# RC_Transmitter_TX_FINAL_v4_4.net
KiCad netlist of a schematic drawn in EAGLE
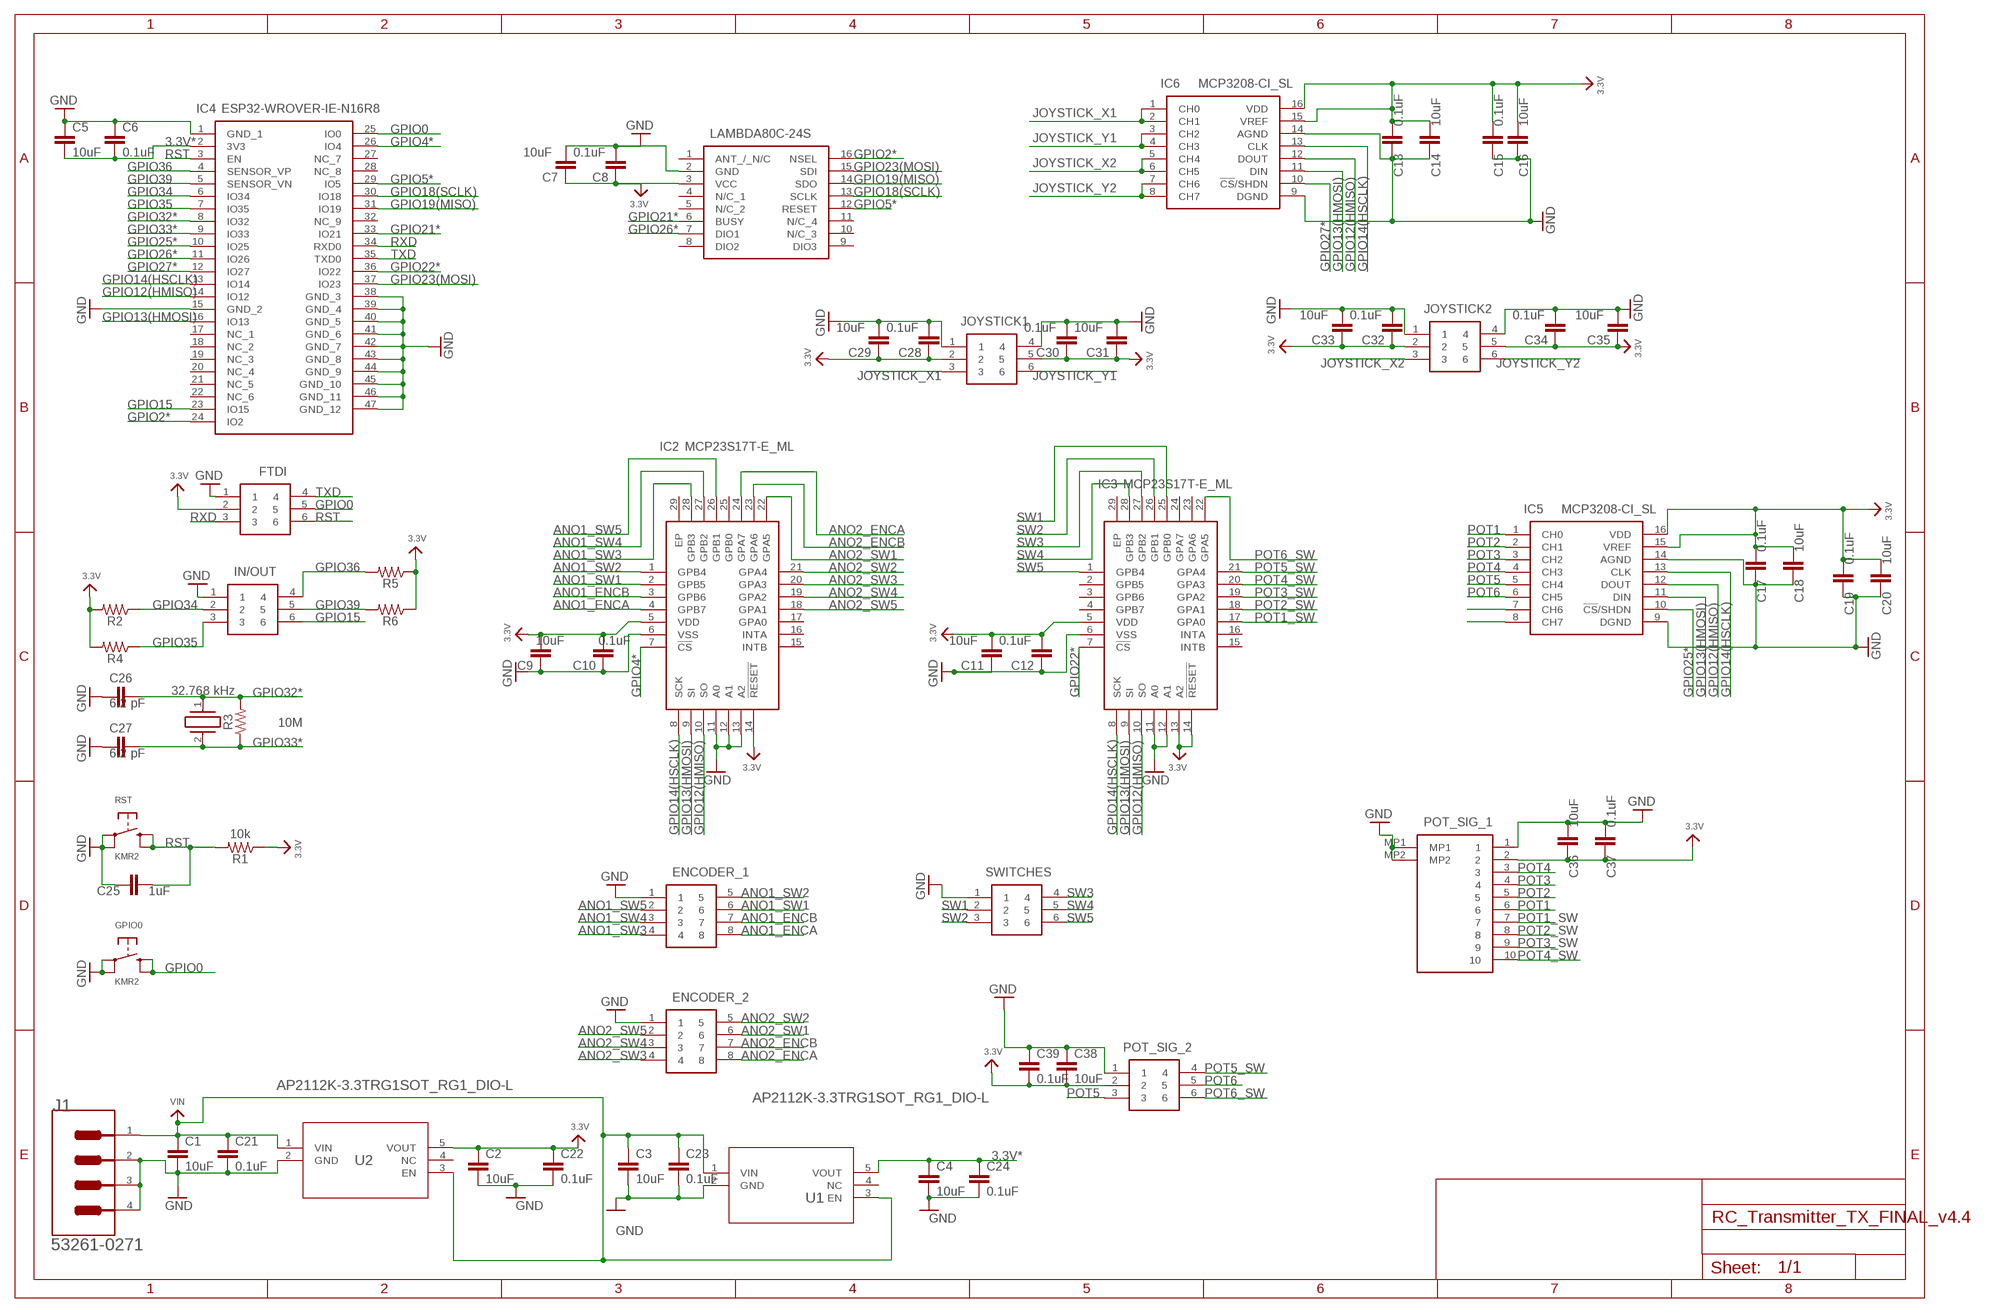
[diagram p0: schematic, sheet 1]

(export (version "E")
  (design (tool "Eeschema 10.0.6"))
  (components
    (comp (ref "C1")
      (value "10uF")
      (footprint "eagle-import:0805")
      (libsource (lib "eagle-import") (part "10UF-0805-10V-10%"))
    )
    (comp (ref "C2")
      (value "10uF")
      (footprint "eagle-import:0805")
      (libsource (lib "eagle-import") (part "10UF-0805-10V-10%"))
    )
    (comp (ref "C3")
      (value "10uF")
      (footprint "eagle-import:0805")
      (libsource (lib "eagle-import") (part "10UF-0805-10V-10%"))
    )
    (comp (ref "C4")
      (value "10uF")
      (footprint "eagle-import:0805")
      (libsource (lib "eagle-import") (part "10UF-0805-10V-10%"))
    )
    (comp (ref "C5")
      (value "10uF")
      (footprint "eagle-import:0805")
      (libsource (lib "eagle-import") (part "10UF-0805-10V-10%"))
    )
    (comp (ref "C6")
      (value "0.1uF")
      (footprint "eagle-import:0805")
      (libsource (lib "eagle-import") (part "10UF-0805-10V-10%"))
    )
    (comp (ref "C7")
      (value "10uF")
      (footprint "eagle-import:0805")
      (libsource (lib "eagle-import") (part "10UF-0805-10V-10%"))
    )
    (comp (ref "C8")
      (value "0.1uF")
      (footprint "eagle-import:0805")
      (libsource (lib "eagle-import") (part "10UF-0805-10V-10%"))
    )
    (comp (ref "C9")
      (value "10uF")
      (footprint "eagle-import:0805")
      (libsource (lib "eagle-import") (part "10UF-0805-10V-10%"))
    )
    (comp (ref "C10")
      (value "0.1uF")
      (footprint "eagle-import:0805")
      (libsource (lib "eagle-import") (part "10UF-0805-10V-10%"))
    )
    (comp (ref "C11")
      (value "10uF")
      (footprint "eagle-import:0805")
      (libsource (lib "eagle-import") (part "10UF-0805-10V-10%"))
    )
    (comp (ref "C12")
      (value "0.1uF")
      (footprint "eagle-import:0805")
      (libsource (lib "eagle-import") (part "10UF-0805-10V-10%"))
    )
    (comp (ref "C13")
      (value "0.1uF")
      (footprint "eagle-import:0805")
      (libsource (lib "eagle-import") (part "10UF-0805-10V-10%"))
    )
    (comp (ref "C14")
      (value "10uF")
      (footprint "eagle-import:0805")
      (libsource (lib "eagle-import") (part "10UF-0805-10V-10%"))
    )
    (comp (ref "C15")
      (value "0.1uF")
      (footprint "eagle-import:0805")
      (libsource (lib "eagle-import") (part "10UF-0805-10V-10%"))
    )
    (comp (ref "C16")
      (value "10uF")
      (footprint "eagle-import:0805")
      (libsource (lib "eagle-import") (part "10UF-0805-10V-10%"))
    )
    (comp (ref "C17")
      (value "0.1uF")
      (footprint "eagle-import:0805")
      (libsource (lib "eagle-import") (part "10UF-0805-10V-10%"))
    )
    (comp (ref "C18")
      (value "10uF")
      (footprint "eagle-import:0805")
      (libsource (lib "eagle-import") (part "10UF-0805-10V-10%"))
    )
    (comp (ref "C19")
      (value "0.1uF")
      (footprint "eagle-import:0805")
      (libsource (lib "eagle-import") (part "10UF-0805-10V-10%"))
    )
    (comp (ref "C20")
      (value "10uF")
      (footprint "eagle-import:0805")
      (libsource (lib "eagle-import") (part "10UF-0805-10V-10%"))
    )
    (comp (ref "C21")
      (value "0.1uF")
      (footprint "eagle-import:0805")
      (libsource (lib "eagle-import") (part "10UF-0805-10V-10%"))
    )
    (comp (ref "C22")
      (value "0.1uF")
      (footprint "eagle-import:0805")
      (libsource (lib "eagle-import") (part "10UF-0805-10V-10%"))
    )
    (comp (ref "C23")
      (value "0.1uF")
      (footprint "eagle-import:0805")
      (libsource (lib "eagle-import") (part "10UF-0805-10V-10%"))
    )
    (comp (ref "C24")
      (value "0.1uF")
      (footprint "eagle-import:0805")
      (libsource (lib "eagle-import") (part "10UF-0805-10V-10%"))
    )
    (comp (ref "C25")
      (value "1uF")
      (footprint "eagle-import:0805")
      (libsource (lib "eagle-import") (part "10UF-0805-10V-10%"))
    )
    (comp (ref "C26")
      (value "6.2 pF")
      (footprint "eagle-import:0805")
      (libsource (lib "eagle-import") (part "10UF-0805-10V-10%"))
    )
    (comp (ref "C27")
      (value "6.2 pF")
      (footprint "eagle-import:0805")
      (libsource (lib "eagle-import") (part "10UF-0805-10V-10%"))
    )
    (comp (ref "C28")
      (value "0.1uF")
      (footprint "eagle-import:0805")
      (libsource (lib "eagle-import") (part "10UF-0805-10V-10%"))
    )
    (comp (ref "C29")
      (value "10uF")
      (footprint "eagle-import:0805")
      (libsource (lib "eagle-import") (part "10UF-0805-10V-10%"))
    )
    (comp (ref "C30")
      (value "0.1uF")
      (footprint "eagle-import:0805")
      (libsource (lib "eagle-import") (part "10UF-0805-10V-10%"))
    )
    (comp (ref "C31")
      (value "10uF")
      (footprint "eagle-import:0805")
      (libsource (lib "eagle-import") (part "10UF-0805-10V-10%"))
    )
    (comp (ref "C32")
      (value "0.1uF")
      (footprint "eagle-import:0805")
      (libsource (lib "eagle-import") (part "10UF-0805-10V-10%"))
    )
    (comp (ref "C33")
      (value "10uF")
      (footprint "eagle-import:0805")
      (libsource (lib "eagle-import") (part "10UF-0805-10V-10%"))
    )
    (comp (ref "C34")
      (value "0.1uF")
      (footprint "eagle-import:0805")
      (libsource (lib "eagle-import") (part "10UF-0805-10V-10%"))
    )
    (comp (ref "C35")
      (value "10uF")
      (footprint "eagle-import:0805")
      (libsource (lib "eagle-import") (part "10UF-0805-10V-10%"))
    )
    (comp (ref "C36")
      (value "10uF")
      (footprint "eagle-import:0805")
      (libsource (lib "eagle-import") (part "10UF-0805-10V-10%"))
    )
    (comp (ref "C37")
      (value "0.1uF")
      (footprint "eagle-import:0805")
      (libsource (lib "eagle-import") (part "10UF-0805-10V-10%"))
    )
    (comp (ref "C38")
      (value "10uF")
      (footprint "eagle-import:0805")
      (libsource (lib "eagle-import") (part "10UF-0805-10V-10%"))
    )
    (comp (ref "C39")
      (value "0.1uF")
      (footprint "eagle-import:0805")
      (libsource (lib "eagle-import") (part "10UF-0805-10V-10%"))
    )
    (comp (ref "CRYSTAL")
      (value "32.768 kHz")
      (footprint "eagle-import:ECX327CDX1293")
      (fields
        (field (name "ARROW_PART_NUMBER") "ECX-.327-CDX-1293")
        (field (name "MOUSER_PART_NUMBER") "520-ECX-.327CDX-1293")
        (field (name "ARROW_PART_NUMBER_1") "Crystal")
      )
      (libsource (lib "eagle-import") (part "ECX-.327-CDX-1293"))
    )
    (comp (ref "ENCODER_1")
      (value "0532610871")
      (footprint "eagle-import:53261-0871")
      (libsource (lib "eagle-import") (part "0532610871"))
    )
    (comp (ref "ENCODER_2")
      (value "0532610871")
      (footprint "eagle-import:53261-0871")
      (libsource (lib "eagle-import") (part "0532610871"))
    )
    (comp (ref "FTDI")
      (value "0532610671")
      (footprint "eagle-import:0532610671")
      (libsource (lib "eagle-import") (part "0532610671"))
    )
    (comp (ref "GPIO0")
      (value "KMR2")
      (footprint "eagle-import:BTN_KMR2_4.6X2.8")
      (libsource (lib "eagle-import") (part "SWITCH_TACT_SMT4.6X2.8"))
    )
    (comp (ref "IC1")
      (value "LAMBDA80C-24S")
      (footprint "eagle-import:LAMBDA80C24S")
      (fields (field (name "MOUSER_PART_NUMBER") "223-LAMBDA80C-24S"))
      (libsource (lib "eagle-import") (part "LAMBDA80C-24S"))
    )
    (comp (ref "IC2")
      (value "MCP23S17T-E_ML")
      (footprint "eagle-import:QFN65P600X600X100-29N")
      (fields
        (field (name "ARROW_PART_NUMBER") "MCP23S17T-E/ML")
        (field (name "MOUSER_PART_NUMBER") "579-MCP23S17T-E/ML")
      )
      (libsource (lib "eagle-import") (part "MCP23S17T-E_ML"))
    )
    (comp (ref "IC3")
      (value "MCP23S17T-E_ML")
      (footprint "eagle-import:QFN65P600X600X100-29N")
      (fields
        (field (name "ARROW_PART_NUMBER") "MCP23S17T-E/ML")
        (field (name "MOUSER_PART_NUMBER") "579-MCP23S17T-E/ML")
      )
      (libsource (lib "eagle-import") (part "MCP23S17T-E_ML"))
    )
    (comp (ref "IC4")
      (value "ESP32-WROVER-IE-N16R8")
      (footprint "eagle-import:ESP32WROVERIEN16R8")
      (fields
        (field (name "MANUFACTURER_PART_NUMBER") "ESP32-Wrover-IE-N16R8")
        (field (name "MOUSER_PART_NUMBER") "356-ESP32WRVIE2864UC")
      )
      (libsource (lib "eagle-import") (part "ESP32-WROVER-IE-N16R8"))
    )
    (comp (ref "IC5")
      (value "MCP3208-CI_SL")
      (footprint "eagle-import:SOIC127P600X175-16N")
      (fields
        (field (name "ARROW_PART_NUMBER") "MCP3208-CI/SL")
        (field (name "MOUSER_PART_NUMBER") "579-MCP3208CISL")
      )
      (libsource (lib "eagle-import") (part "MCP3208-CI_SL"))
    )
    (comp (ref "IC6")
      (value "MCP3208-CI_SL")
      (footprint "eagle-import:SOIC127P600X175-16N")
      (fields
        (field (name "ARROW_PART_NUMBER") "MCP3208-CI/SL")
        (field (name "MOUSER_PART_NUMBER") "579-MCP3208CISL")
      )
      (libsource (lib "eagle-import") (part "MCP3208-CI_SL"))
    )
    (comp (ref "IN/OUT")
      (value "0532610671")
      (footprint "eagle-import:0532610671")
      (libsource (lib "eagle-import") (part "0532610671"))
    )
    (comp (ref "J1")
      (value "MOLEX_53261-0271MOLEX_53261-0271_0_0")
      (footprint "eagle-import:MOLEX_53261-0271_0")
      (fields
        (field (name "DIGIKEY_PART_NUMBER") "WM7620CT-ND")
        (field (name "MF") "Molex")
        (field (name "MOUSER_PART_NUMBER") "538-53261-0271")
      )
      (libsource (lib "eagle-import") (part "MOLEX_53261-0271MOLEX_53261-0271_0_0"))
    )
    (comp (ref "JOYSTICK1")
      (value "0532610671")
      (footprint "eagle-import:0532610671")
      (libsource (lib "eagle-import") (part "0532610671"))
    )
    (comp (ref "JOYSTICK2")
      (value "0532610671")
      (footprint "eagle-import:0532610671")
      (libsource (lib "eagle-import") (part "0532610671"))
    )
    (comp (ref "POT_SIG_1")
      (value "0532611071")
      (footprint "eagle-import:0532611071")
      (libsource (lib "eagle-import") (part "0532611071"))
    )
    (comp (ref "POT_SIG_2")
      (value "0532610671")
      (footprint "eagle-import:0532610671")
      (libsource (lib "eagle-import") (part "0532610671"))
    )
    (comp (ref "R1")
      (value "10k")
      (footprint "eagle-import:0603")
      (libsource (lib "eagle-import") (part "0OHM-0603-1/10W-5%"))
    )
    (comp (ref "R2")
      (value "10k")
      (footprint "eagle-import:0603")
      (libsource (lib "eagle-import") (part "0OHM-0603-1/10W-5%"))
    )
    (comp (ref "R3")
      (value "10M")
      (footprint "eagle-import:0603")
      (libsource (lib "eagle-import") (part "0OHM-0603-1/10W-5%"))
    )
    (comp (ref "R4")
      (value "10k")
      (footprint "eagle-import:0603")
      (libsource (lib "eagle-import") (part "0OHM-0603-1/10W-5%"))
    )
    (comp (ref "R5")
      (value "10k")
      (footprint "eagle-import:0603")
      (libsource (lib "eagle-import") (part "0OHM-0603-1/10W-5%"))
    )
    (comp (ref "R6")
      (value "10k")
      (footprint "eagle-import:0603")
      (libsource (lib "eagle-import") (part "0OHM-0603-1/10W-5%"))
    )
    (comp (ref "RST")
      (value "KMR2")
      (footprint "eagle-import:BTN_KMR2_4.6X2.8")
      (libsource (lib "eagle-import") (part "SWITCH_TACT_SMT4.6X2.8"))
    )
    (comp (ref "SWITCHES")
      (value "0532610671")
      (footprint "eagle-import:0532610671")
      (libsource (lib "eagle-import") (part "0532610671"))
    )
    (comp (ref "U1")
      (value "AP2112K-3.3TRG1SOT_RG1_DIO-L")
      (footprint "eagle-import:SOT_RG1_DIO-L")
      (fields
        (field (name "MANUFACTURER_PART_NUMBER") "AP2112K-3.3TRG1")
        (field (name "COPYRIGHT") "Copyright (C) 2023 Ultra Librarian. All rights reserved.")
      )
      (libsource (lib "eagle-import") (part "AP2112K-3.3TRG1SOT_RG1_DIO-L"))
    )
    (comp (ref "U2")
      (value "AP2112K-3.3TRG1SOT_RG1_DIO-L")
      (footprint "eagle-import:SOT_RG1_DIO-L")
      (fields
        (field (name "MANUFACTURER_PART_NUMBER") "AP2112K-3.3TRG1")
        (field (name "COPYRIGHT") "Copyright (C) 2023 Ultra Librarian. All rights reserved.")
      )
      (libsource (lib "eagle-import") (part "AP2112K-3.3TRG1SOT_RG1_DIO-L"))
    )
  )
  (nets
    (net (code "1") (name "/3.3V*") (class "Default")
      (node (ref "C24") (pin "1") (pinfunction "1_1") (pintype "passive"))
      (node (ref "C4") (pin "1") (pinfunction "1_1") (pintype "passive"))
      (node (ref "C5") (pin "2") (pinfunction "2_2") (pintype "passive"))
      (node (ref "C6") (pin "2") (pinfunction "2_2") (pintype "passive"))
      (node (ref "IC4") (pin "2") (pinfunction "3V3_2") (pintype "bidirectional"))
      (node (ref "U1") (pin "5") (pinfunction "VOUT_5") (pintype "passive"))
    )
    (net (code "2") (name "/ANO1_ENCA") (class "Default")
      (node (ref "ENCODER_1") (pin "8") (pinfunction "8_8") (pintype "bidirectional"))
      (node (ref "IC2") (pin "4") (pinfunction "GPB7_4") (pintype "bidirectional"))
    )
    (net (code "3") (name "/ANO1_ENCB") (class "Default")
      (node (ref "ENCODER_1") (pin "7") (pinfunction "7_7") (pintype "bidirectional"))
      (node (ref "IC2") (pin "3") (pinfunction "GPB6_3") (pintype "bidirectional"))
    )
    (net (code "4") (name "/ANO1_SW1") (class "Default")
      (node (ref "ENCODER_1") (pin "6") (pinfunction "6_6") (pintype "bidirectional"))
      (node (ref "IC2") (pin "2") (pinfunction "GPB5_2") (pintype "bidirectional"))
    )
    (net (code "5") (name "/ANO1_SW2") (class "Default")
      (node (ref "ENCODER_1") (pin "5") (pinfunction "5_5") (pintype "bidirectional"))
      (node (ref "IC2") (pin "1") (pinfunction "GPB4_1") (pintype "bidirectional"))
    )
    (net (code "6") (name "/ANO1_SW3") (class "Default")
      (node (ref "ENCODER_1") (pin "4") (pinfunction "4_4") (pintype "bidirectional"))
      (node (ref "IC2") (pin "28") (pinfunction "GPB3_28") (pintype "bidirectional"))
    )
    (net (code "7") (name "/ANO1_SW4") (class "Default")
      (node (ref "ENCODER_1") (pin "3") (pinfunction "3_3") (pintype "bidirectional"))
      (node (ref "IC2") (pin "27") (pinfunction "GPB2_27") (pintype "bidirectional"))
    )
    (net (code "8") (name "/ANO1_SW5") (class "Default")
      (node (ref "ENCODER_1") (pin "2") (pinfunction "2_2") (pintype "bidirectional"))
      (node (ref "IC2") (pin "26") (pinfunction "GPB1_26") (pintype "bidirectional"))
    )
    (net (code "9") (name "/ANO2_ENCA") (class "Default")
      (node (ref "ENCODER_2") (pin "8") (pinfunction "8_8") (pintype "bidirectional"))
      (node (ref "IC2") (pin "24") (pinfunction "GPA7_24") (pintype "bidirectional"))
    )
    (net (code "10") (name "/ANO2_ENCB") (class "Default")
      (node (ref "ENCODER_2") (pin "7") (pinfunction "7_7") (pintype "bidirectional"))
      (node (ref "IC2") (pin "23") (pinfunction "GPA6_23") (pintype "bidirectional"))
    )
    (net (code "11") (name "/ANO2_SW1") (class "Default")
      (node (ref "ENCODER_2") (pin "6") (pinfunction "6_6") (pintype "bidirectional"))
      (node (ref "IC2") (pin "22") (pinfunction "GPA5_22") (pintype "bidirectional"))
    )
    (net (code "12") (name "/ANO2_SW2") (class "Default")
      (node (ref "ENCODER_2") (pin "5") (pinfunction "5_5") (pintype "bidirectional"))
      (node (ref "IC2") (pin "21") (pinfunction "GPA4_21") (pintype "bidirectional"))
    )
    (net (code "13") (name "/ANO2_SW3") (class "Default")
      (node (ref "ENCODER_2") (pin "4") (pinfunction "4_4") (pintype "bidirectional"))
      (node (ref "IC2") (pin "20") (pinfunction "GPA3_20") (pintype "bidirectional"))
    )
    (net (code "14") (name "/ANO2_SW4") (class "Default")
      (node (ref "ENCODER_2") (pin "3") (pinfunction "3_3") (pintype "bidirectional"))
      (node (ref "IC2") (pin "19") (pinfunction "GPA2_19") (pintype "bidirectional"))
    )
    (net (code "15") (name "/ANO2_SW5") (class "Default")
      (node (ref "ENCODER_2") (pin "2") (pinfunction "2_2") (pintype "bidirectional"))
      (node (ref "IC2") (pin "18") (pinfunction "GPA1_18") (pintype "bidirectional"))
    )
    (net (code "16") (name "/GPIO0") (class "Default")
      (node (ref "FTDI") (pin "5") (pinfunction "5_5") (pintype "bidirectional"))
      (node (ref "GPIO0") (pin "B") (pinfunction "S_B") (pintype "passive"))
      (node (ref "GPIO0") (pin "B'") (pinfunction "S1_B'") (pintype "passive"))
      (node (ref "IC4") (pin "25") (pinfunction "IO0_25") (pintype "bidirectional"))
    )
    (net (code "17") (name "/GPIO2*") (class "Default")
      (node (ref "IC1") (pin "16") (pinfunction "NSEL_16") (pintype "bidirectional"))
      (node (ref "IC4") (pin "24") (pinfunction "IO2_24") (pintype "bidirectional"))
    )
    (net (code "18") (name "/GPIO4*") (class "Default")
      (node (ref "IC2") (pin "7") (pinfunction "~{CS}_7") (pintype "bidirectional"))
      (node (ref "IC4") (pin "26") (pinfunction "IO4_26") (pintype "bidirectional"))
    )
    (net (code "19") (name "/GPIO5*") (class "Default")
      (node (ref "IC1") (pin "12") (pinfunction "RESET_12") (pintype "bidirectional"))
      (node (ref "IC4") (pin "29") (pinfunction "IO5_29") (pintype "bidirectional"))
    )
    (net (code "20") (name "/GPIO12(HMISO)") (class "Default")
      (node (ref "IC2") (pin "10") (pinfunction "SO_10") (pintype "bidirectional"))
      (node (ref "IC3") (pin "10") (pinfunction "SO_10") (pintype "bidirectional"))
      (node (ref "IC4") (pin "14") (pinfunction "IO12_14") (pintype "bidirectional"))
      (node (ref "IC5") (pin "12") (pinfunction "DOUT_12") (pintype "bidirectional"))
      (node (ref "IC6") (pin "12") (pinfunction "DOUT_12") (pintype "bidirectional"))
    )
    (net (code "21") (name "/GPIO13(HMOSI)") (class "Default")
      (node (ref "IC2") (pin "9") (pinfunction "SI_9") (pintype "bidirectional"))
      (node (ref "IC3") (pin "9") (pinfunction "SI_9") (pintype "bidirectional"))
      (node (ref "IC4") (pin "16") (pinfunction "IO13_16") (pintype "bidirectional"))
      (node (ref "IC5") (pin "11") (pinfunction "DIN_11") (pintype "bidirectional"))
      (node (ref "IC6") (pin "11") (pinfunction "DIN_11") (pintype "bidirectional"))
    )
    (net (code "22") (name "/GPIO14(HSCLK)") (class "Default")
      (node (ref "IC2") (pin "8") (pinfunction "SCK_8") (pintype "bidirectional"))
      (node (ref "IC3") (pin "8") (pinfunction "SCK_8") (pintype "bidirectional"))
      (node (ref "IC4") (pin "13") (pinfunction "IO14_13") (pintype "bidirectional"))
      (node (ref "IC5") (pin "13") (pinfunction "CLK_13") (pintype "bidirectional"))
      (node (ref "IC6") (pin "13") (pinfunction "CLK_13") (pintype "bidirectional"))
    )
    (net (code "23") (name "/GPIO15") (class "Default")
      (node (ref "IC4") (pin "23") (pinfunction "IO15_23") (pintype "bidirectional"))
      (node (ref "IN/OUT") (pin "6") (pinfunction "6_6") (pintype "bidirectional"))
    )
    (net (code "24") (name "/GPIO18(SCLK)") (class "Default")
      (node (ref "IC1") (pin "13") (pinfunction "SCLK_13") (pintype "bidirectional"))
      (node (ref "IC4") (pin "30") (pinfunction "IO18_30") (pintype "bidirectional"))
    )
    (net (code "25") (name "/GPIO19(MISO)") (class "Default")
      (node (ref "IC1") (pin "14") (pinfunction "SDO_14") (pintype "bidirectional"))
      (node (ref "IC4") (pin "31") (pinfunction "IO19_31") (pintype "bidirectional"))
    )
    (net (code "26") (name "/GPIO21*") (class "Default")
      (node (ref "IC1") (pin "6") (pinfunction "BUSY_6") (pintype "bidirectional"))
      (node (ref "IC4") (pin "33") (pinfunction "IO21_33") (pintype "bidirectional"))
    )
    (net (code "27") (name "/GPIO22*") (class "Default")
      (node (ref "IC3") (pin "7") (pinfunction "~{CS}_7") (pintype "bidirectional"))
      (node (ref "IC4") (pin "36") (pinfunction "IO22_36") (pintype "bidirectional"))
    )
    (net (code "28") (name "/GPIO23(MOSI)") (class "Default")
      (node (ref "IC1") (pin "15") (pinfunction "SDI_15") (pintype "bidirectional"))
      (node (ref "IC4") (pin "37") (pinfunction "IO23_37") (pintype "bidirectional"))
    )
    (net (code "29") (name "/GPIO25*") (class "Default")
      (node (ref "IC4") (pin "10") (pinfunction "IO25_10") (pintype "bidirectional"))
      (node (ref "IC5") (pin "10") (pinfunction "~{CS}/SHDN_10") (pintype "bidirectional"))
    )
    (net (code "30") (name "/GPIO26*") (class "Default")
      (node (ref "IC1") (pin "7") (pinfunction "DIO1_7") (pintype "bidirectional"))
      (node (ref "IC4") (pin "11") (pinfunction "IO26_11") (pintype "bidirectional"))
    )
    (net (code "31") (name "/GPIO27*") (class "Default")
      (node (ref "IC4") (pin "12") (pinfunction "IO27_12") (pintype "bidirectional"))
      (node (ref "IC6") (pin "10") (pinfunction "~{CS}/SHDN_10") (pintype "bidirectional"))
    )
    (net (code "32") (name "/GPIO32*") (class "Default")
      (node (ref "C26") (pin "2") (pinfunction "2_2") (pintype "passive"))
      (node (ref "CRYSTAL") (pin "1") (pinfunction "X1_1") (pintype "bidirectional"))
      (node (ref "IC4") (pin "8") (pinfunction "IO32_8") (pintype "bidirectional"))
      (node (ref "R3") (pin "2") (pinfunction "2_2") (pintype "passive"))
    )
    (net (code "33") (name "/GPIO33*") (class "Default")
      (node (ref "C27") (pin "2") (pinfunction "2_2") (pintype "passive"))
      (node (ref "CRYSTAL") (pin "2") (pinfunction "X2_2") (pintype "bidirectional"))
      (node (ref "IC4") (pin "9") (pinfunction "IO33_9") (pintype "bidirectional"))
      (node (ref "R3") (pin "1") (pinfunction "1_1") (pintype "passive"))
    )
    (net (code "34") (name "/GPIO34") (class "Default")
      (node (ref "IC4") (pin "6") (pinfunction "IO34_6") (pintype "bidirectional"))
      (node (ref "IN/OUT") (pin "2") (pinfunction "2_2") (pintype "bidirectional"))
      (node (ref "R2") (pin "1") (pinfunction "1_1") (pintype "passive"))
    )
    (net (code "35") (name "/GPIO35") (class "Default")
      (node (ref "IC4") (pin "7") (pinfunction "IO35_7") (pintype "bidirectional"))
      (node (ref "IN/OUT") (pin "3") (pinfunction "3_3") (pintype "bidirectional"))
      (node (ref "R4") (pin "1") (pinfunction "1_1") (pintype "passive"))
    )
    (net (code "36") (name "/GPIO36") (class "Default")
      (node (ref "IC4") (pin "4") (pinfunction "SENSOR_VP_4") (pintype "bidirectional"))
      (node (ref "IN/OUT") (pin "4") (pinfunction "4_4") (pintype "bidirectional"))
      (node (ref "R5") (pin "2") (pinfunction "2_2") (pintype "passive"))
    )
    (net (code "37") (name "/GPIO39") (class "Default")
      (node (ref "IC4") (pin "5") (pinfunction "SENSOR_VN_5") (pintype "bidirectional"))
      (node (ref "IN/OUT") (pin "5") (pinfunction "5_5") (pintype "bidirectional"))
      (node (ref "R6") (pin "2") (pinfunction "2_2") (pintype "passive"))
    )
    (net (code "38") (name "/JOYSTICK_X1") (class "Default")
      (node (ref "IC6") (pin "1") (pinfunction "CH0_1") (pintype "bidirectional"))
      (node (ref "IC6") (pin "2") (pinfunction "CH1_2") (pintype "bidirectional"))
      (node (ref "JOYSTICK1") (pin "3") (pinfunction "3_3") (pintype "bidirectional"))
    )
    (net (code "39") (name "/JOYSTICK_X2") (class "Default")
      (node (ref "IC6") (pin "5") (pinfunction "CH4_5") (pintype "bidirectional"))
      (node (ref "IC6") (pin "6") (pinfunction "CH5_6") (pintype "bidirectional"))
      (node (ref "JOYSTICK2") (pin "3") (pinfunction "3_3") (pintype "bidirectional"))
    )
    (net (code "40") (name "/JOYSTICK_Y1") (class "Default")
      (node (ref "IC6") (pin "3") (pinfunction "CH2_3") (pintype "bidirectional"))
      (node (ref "IC6") (pin "4") (pinfunction "CH3_4") (pintype "bidirectional"))
      (node (ref "JOYSTICK1") (pin "6") (pinfunction "6_6") (pintype "bidirectional"))
    )
    (net (code "41") (name "/JOYSTICK_Y2") (class "Default")
      (node (ref "IC6") (pin "7") (pinfunction "CH6_7") (pintype "bidirectional"))
      (node (ref "IC6") (pin "8") (pinfunction "CH7_8") (pintype "bidirectional"))
      (node (ref "JOYSTICK2") (pin "6") (pinfunction "6_6") (pintype "bidirectional"))
    )
    (net (code "42") (name "/POT1") (class "Default")
      (node (ref "IC5") (pin "1") (pinfunction "CH0_1") (pintype "bidirectional"))
      (node (ref "POT_SIG_1") (pin "6") (pinfunction "6_6") (pintype "bidirectional"))
    )
    (net (code "43") (name "/POT1_SW") (class "Default")
      (node (ref "IC3") (pin "17") (pinfunction "GPA0_17") (pintype "bidirectional"))
      (node (ref "POT_SIG_1") (pin "7") (pinfunction "7_7") (pintype "bidirectional"))
    )
    (net (code "44") (name "/POT2") (class "Default")
      (node (ref "IC5") (pin "2") (pinfunction "CH1_2") (pintype "bidirectional"))
      (node (ref "POT_SIG_1") (pin "5") (pinfunction "5_5") (pintype "bidirectional"))
    )
    (net (code "45") (name "/POT2_SW") (class "Default")
      (node (ref "IC3") (pin "18") (pinfunction "GPA1_18") (pintype "bidirectional"))
      (node (ref "POT_SIG_1") (pin "8") (pinfunction "8_8") (pintype "bidirectional"))
    )
    (net (code "46") (name "/POT3") (class "Default")
      (node (ref "IC5") (pin "3") (pinfunction "CH2_3") (pintype "bidirectional"))
      (node (ref "POT_SIG_1") (pin "4") (pinfunction "4_4") (pintype "bidirectional"))
    )
    (net (code "47") (name "/POT3_SW") (class "Default")
      (node (ref "IC3") (pin "19") (pinfunction "GPA2_19") (pintype "bidirectional"))
      (node (ref "POT_SIG_1") (pin "9") (pinfunction "9_9") (pintype "bidirectional"))
    )
    (net (code "48") (name "/POT4") (class "Default")
      (node (ref "IC5") (pin "4") (pinfunction "CH3_4") (pintype "bidirectional"))
      (node (ref "POT_SIG_1") (pin "3") (pinfunction "3_3") (pintype "bidirectional"))
    )
    (net (code "49") (name "/POT4_SW") (class "Default")
      (node (ref "IC3") (pin "20") (pinfunction "GPA3_20") (pintype "bidirectional"))
      (node (ref "POT_SIG_1") (pin "10") (pinfunction "10_10") (pintype "bidirectional"))
    )
    (net (code "50") (name "/POT5") (class "Default")
      (node (ref "IC5") (pin "5") (pinfunction "CH4_5") (pintype "bidirectional"))
      (node (ref "POT_SIG_2") (pin "3") (pinfunction "3_3") (pintype "bidirectional"))
    )
    (net (code "51") (name "/POT5_SW") (class "Default")
      (node (ref "IC3") (pin "21") (pinfunction "GPA4_21") (pintype "bidirectional"))
      (node (ref "POT_SIG_2") (pin "4") (pinfunction "4_4") (pintype "bidirectional"))
    )
    (net (code "52") (name "/POT6") (class "Default")
      (node (ref "IC5") (pin "6") (pinfunction "CH5_6") (pintype "bidirectional"))
      (node (ref "POT_SIG_2") (pin "5") (pinfunction "5_5") (pintype "bidirectional"))
    )
    (net (code "53") (name "/POT6_SW") (class "Default")
      (node (ref "IC3") (pin "22") (pinfunction "GPA5_22") (pintype "bidirectional"))
      (node (ref "POT_SIG_2") (pin "6") (pinfunction "6_6") (pintype "bidirectional"))
    )
    (net (code "54") (name "/RST") (class "Default")
      (node (ref "C25") (pin "2") (pinfunction "2_2") (pintype "passive"))
      (node (ref "FTDI") (pin "6") (pinfunction "6_6") (pintype "bidirectional"))
      (node (ref "IC4") (pin "3") (pinfunction "EN_3") (pintype "bidirectional"))
      (node (ref "R1") (pin "2") (pinfunction "2_2") (pintype "passive"))
      (node (ref "RST") (pin "B") (pinfunction "S_B") (pintype "passive"))
      (node (ref "RST") (pin "B'") (pinfunction "S1_B'") (pintype "passive"))
    )
    (net (code "55") (name "/RXD") (class "Default")
      (node (ref "FTDI") (pin "3") (pinfunction "3_3") (pintype "bidirectional"))
      (node (ref "IC4") (pin "34") (pinfunction "RXD0_34") (pintype "bidirectional"))
    )
    (net (code "56") (name "/SW1") (class "Default")
      (node (ref "IC3") (pin "25") (pinfunction "GPB0_25") (pintype "bidirectional"))
      (node (ref "SWITCHES") (pin "2") (pinfunction "2_2") (pintype "bidirectional"))
    )
    (net (code "57") (name "/SW2") (class "Default")
      (node (ref "IC3") (pin "26") (pinfunction "GPB1_26") (pintype "bidirectional"))
      (node (ref "SWITCHES") (pin "3") (pinfunction "3_3") (pintype "bidirectional"))
    )
    (net (code "58") (name "/SW3") (class "Default")
      (node (ref "IC3") (pin "27") (pinfunction "GPB2_27") (pintype "bidirectional"))
      (node (ref "SWITCHES") (pin "4") (pinfunction "4_4") (pintype "bidirectional"))
    )
    (net (code "59") (name "/SW4") (class "Default")
      (node (ref "IC3") (pin "28") (pinfunction "GPB3_28") (pintype "bidirectional"))
      (node (ref "SWITCHES") (pin "5") (pinfunction "5_5") (pintype "bidirectional"))
    )
    (net (code "60") (name "/SW5") (class "Default")
      (node (ref "IC3") (pin "1") (pinfunction "GPB4_1") (pintype "bidirectional"))
      (node (ref "SWITCHES") (pin "6") (pinfunction "6_6") (pintype "bidirectional"))
    )
    (net (code "61") (name "/TXD") (class "Default")
      (node (ref "FTDI") (pin "4") (pinfunction "4_4") (pintype "bidirectional"))
      (node (ref "IC4") (pin "35") (pinfunction "TXD0_35") (pintype "bidirectional"))
    )
    (net (code "62") (name "3.3V") (class "Default")
      (node (ref "C10") (pin "2") (pinfunction "2_2") (pintype "passive"))
      (node (ref "C11") (pin "2") (pinfunction "2_2") (pintype "passive"))
      (node (ref "C12") (pin "2") (pinfunction "2_2") (pintype "passive"))
      (node (ref "C13") (pin "2") (pinfunction "2_2") (pintype "passive"))
      (node (ref "C14") (pin "2") (pinfunction "2_2") (pintype "passive"))
      (node (ref "C15") (pin "2") (pinfunction "2_2") (pintype "passive"))
      (node (ref "C16") (pin "2") (pinfunction "2_2") (pintype "passive"))
      (node (ref "C17") (pin "2") (pinfunction "2_2") (pintype "passive"))
      (node (ref "C18") (pin "2") (pinfunction "2_2") (pintype "passive"))
      (node (ref "C19") (pin "2") (pinfunction "2_2") (pintype "passive"))
      (node (ref "C2") (pin "1") (pinfunction "1_1") (pintype "passive"))
      (node (ref "C20") (pin "2") (pinfunction "2_2") (pintype "passive"))
      (node (ref "C22") (pin "1") (pinfunction "1_1") (pintype "passive"))
      (node (ref "C28") (pin "1") (pinfunction "1_1") (pintype "passive"))
      (node (ref "C29") (pin "1") (pinfunction "1_1") (pintype "passive"))
      (node (ref "C30") (pin "1") (pinfunction "1_1") (pintype "passive"))
      (node (ref "C31") (pin "1") (pinfunction "1_1") (pintype "passive"))
      (node (ref "C32") (pin "1") (pinfunction "1_1") (pintype "passive"))
      (node (ref "C33") (pin "1") (pinfunction "1_1") (pintype "passive"))
      (node (ref "C34") (pin "1") (pinfunction "1_1") (pintype "passive"))
      (node (ref "C35") (pin "1") (pinfunction "1_1") (pintype "passive"))
      (node (ref "C36") (pin "1") (pinfunction "1_1") (pintype "passive"))
      (node (ref "C37") (pin "1") (pinfunction "1_1") (pintype "passive"))
      (node (ref "C38") (pin "2") (pinfunction "2_2") (pintype "passive"))
      (node (ref "C39") (pin "2") (pinfunction "2_2") (pintype "passive"))
      (node (ref "C7") (pin "1") (pinfunction "1_1") (pintype "passive"))
      (node (ref "C8") (pin "1") (pinfunction "1_1") (pintype "passive"))
      (node (ref "C9") (pin "2") (pinfunction "2_2") (pintype "passive"))
      (node (ref "FTDI") (pin "2") (pinfunction "2_2") (pintype "bidirectional"))
      (node (ref "IC1") (pin "3") (pinfunction "VCC_3") (pintype "bidirectional"))
      (node (ref "IC2") (pin "14") (pinfunction "~{RESET}_14") (pintype "bidirectional"))
      (node (ref "IC2") (pin "5") (pinfunction "VDD_5") (pintype "bidirectional"))
      (node (ref "IC3") (pin "13") (pinfunction "A2_13") (pintype "bidirectional"))
      (node (ref "IC3") (pin "14") (pinfunction "~{RESET}_14") (pintype "bidirectional"))
      (node (ref "IC3") (pin "5") (pinfunction "VDD_5") (pintype "bidirectional"))
      (node (ref "IC5") (pin "15") (pinfunction "VREF_15") (pintype "bidirectional"))
      (node (ref "IC5") (pin "16") (pinfunction "VDD_16") (pintype "bidirectional"))
      (node (ref "IC6") (pin "15") (pinfunction "VREF_15") (pintype "bidirectional"))
      (node (ref "IC6") (pin "16") (pinfunction "VDD_16") (pintype "bidirectional"))
      (node (ref "JOYSTICK1") (pin "2") (pinfunction "2_2") (pintype "bidirectional"))
      (node (ref "JOYSTICK1") (pin "5") (pinfunction "5_5") (pintype "bidirectional"))
      (node (ref "JOYSTICK2") (pin "2") (pinfunction "2_2") (pintype "bidirectional"))
      (node (ref "JOYSTICK2") (pin "5") (pinfunction "5_5") (pintype "bidirectional"))
      (node (ref "POT_SIG_1") (pin "2") (pinfunction "2_2") (pintype "bidirectional"))
      (node (ref "POT_SIG_2") (pin "2") (pinfunction "2_2") (pintype "bidirectional"))
      (node (ref "R1") (pin "1") (pinfunction "1_1") (pintype "passive"))
      (node (ref "R2") (pin "2") (pinfunction "2_2") (pintype "passive"))
      (node (ref "R4") (pin "2") (pinfunction "2_2") (pintype "passive"))
      (node (ref "R5") (pin "1") (pinfunction "1_1") (pintype "passive"))
      (node (ref "R6") (pin "1") (pinfunction "1_1") (pintype "passive"))
      (node (ref "U2") (pin "5") (pinfunction "VOUT_5") (pintype "passive"))
    )
    (net (code "63") (name "GND") (class "Default")
      (node (ref "C1") (pin "2") (pinfunction "2_2") (pintype "passive"))
      (node (ref "C10") (pin "1") (pinfunction "1_1") (pintype "passive"))
      (node (ref "C11") (pin "1") (pinfunction "1_1") (pintype "passive"))
      (node (ref "C12") (pin "1") (pinfunction "1_1") (pintype "passive"))
      (node (ref "C13") (pin "1") (pinfunction "1_1") (pintype "passive"))
      (node (ref "C14") (pin "1") (pinfunction "1_1") (pintype "passive"))
      (node (ref "C15") (pin "1") (pinfunction "1_1") (pintype "passive"))
      (node (ref "C16") (pin "1") (pinfunction "1_1") (pintype "passive"))
      (node (ref "C17") (pin "1") (pinfunction "1_1") (pintype "passive"))
      (node (ref "C18") (pin "1") (pinfunction "1_1") (pintype "passive"))
      (node (ref "C19") (pin "1") (pinfunction "1_1") (pintype "passive"))
      (node (ref "C2") (pin "2") (pinfunction "2_2") (pintype "passive"))
      (node (ref "C20") (pin "1") (pinfunction "1_1") (pintype "passive"))
      (node (ref "C21") (pin "2") (pinfunction "2_2") (pintype "passive"))
      (node (ref "C22") (pin "2") (pinfunction "2_2") (pintype "passive"))
      (node (ref "C23") (pin "2") (pinfunction "2_2") (pintype "passive"))
      (node (ref "C24") (pin "2") (pinfunction "2_2") (pintype "passive"))
      (node (ref "C25") (pin "1") (pinfunction "1_1") (pintype "passive"))
      (node (ref "C26") (pin "1") (pinfunction "1_1") (pintype "passive"))
      (node (ref "C27") (pin "1") (pinfunction "1_1") (pintype "passive"))
      (node (ref "C28") (pin "2") (pinfunction "2_2") (pintype "passive"))
      (node (ref "C29") (pin "2") (pinfunction "2_2") (pintype "passive"))
      (node (ref "C3") (pin "2") (pinfunction "2_2") (pintype "passive"))
      (node (ref "C30") (pin "2") (pinfunction "2_2") (pintype "passive"))
      (node (ref "C31") (pin "2") (pinfunction "2_2") (pintype "passive"))
      (node (ref "C32") (pin "2") (pinfunction "2_2") (pintype "passive"))
      (node (ref "C33") (pin "2") (pinfunction "2_2") (pintype "passive"))
      (node (ref "C34") (pin "2") (pinfunction "2_2") (pintype "passive"))
      (node (ref "C35") (pin "2") (pinfunction "2_2") (pintype "passive"))
      (node (ref "C36") (pin "2") (pinfunction "2_2") (pintype "passive"))
      (node (ref "C37") (pin "2") (pinfunction "2_2") (pintype "passive"))
      (node (ref "C38") (pin "1") (pinfunction "1_1") (pintype "passive"))
      (node (ref "C39") (pin "1") (pinfunction "1_1") (pintype "passive"))
      (node (ref "C4") (pin "2") (pinfunction "2_2") (pintype "passive"))
      (node (ref "C5") (pin "1") (pinfunction "1_1") (pintype "passive"))
      (node (ref "C6") (pin "1") (pinfunction "1_1") (pintype "passive"))
      (node (ref "C7") (pin "2") (pinfunction "2_2") (pintype "passive"))
      (node (ref "C8") (pin "2") (pinfunction "2_2") (pintype "passive"))
      (node (ref "C9") (pin "1") (pinfunction "1_1") (pintype "passive"))
      (node (ref "ENCODER_1") (pin "1") (pinfunction "1_1") (pintype "bidirectional"))
      (node (ref "ENCODER_2") (pin "1") (pinfunction "1_1") (pintype "bidirectional"))
      (node (ref "FTDI") (pin "1") (pinfunction "1_1") (pintype "bidirectional"))
      (node (ref "GPIO0") (pin "A") (pinfunction "P_A") (pintype "passive"))
      (node (ref "GPIO0") (pin "A'") (pinfunction "P1_A'") (pintype "passive"))
      (node (ref "IC1") (pin "2") (pinfunction "GND_2") (pintype "bidirectional"))
      (node (ref "IC2") (pin "11") (pinfunction "A0_11") (pintype "bidirectional"))
      (node (ref "IC2") (pin "12") (pinfunction "A1_12") (pintype "bidirectional"))
      (node (ref "IC2") (pin "13") (pinfunction "A2_13") (pintype "bidirectional"))
      (node (ref "IC2") (pin "6") (pinfunction "VSS_6") (pintype "bidirectional"))
      (node (ref "IC3") (pin "11") (pinfunction "A0_11") (pintype "bidirectional"))
      (node (ref "IC3") (pin "12") (pinfunction "A1_12") (pintype "bidirectional"))
      (node (ref "IC3") (pin "6") (pinfunction "VSS_6") (pintype "bidirectional"))
      (node (ref "IC4") (pin "1") (pinfunction "GND_1_1") (pintype "bidirectional"))
      (node (ref "IC4") (pin "15") (pinfunction "GND_2_15") (pintype "bidirectional"))
      (node (ref "IC4") (pin "38") (pinfunction "GND_3_38") (pintype "bidirectional"))
      (node (ref "IC4") (pin "39") (pinfunction "GND_4_39") (pintype "bidirectional"))
      (node (ref "IC4") (pin "40") (pinfunction "GND_5_40") (pintype "bidirectional"))
      (node (ref "IC4") (pin "41") (pinfunction "GND_6_41") (pintype "bidirectional"))
      (node (ref "IC4") (pin "42") (pinfunction "GND_7_42") (pintype "bidirectional"))
      (node (ref "IC4") (pin "43") (pinfunction "GND_8_43") (pintype "bidirectional"))
      (node (ref "IC4") (pin "44") (pinfunction "GND_9_44") (pintype "bidirectional"))
      (node (ref "IC4") (pin "45") (pinfunction "GND_10_45") (pintype "bidirectional"))
      (node (ref "IC4") (pin "46") (pinfunction "GND_11_46") (pintype "bidirectional"))
      (node (ref "IC4") (pin "47") (pinfunction "GND_12_47") (pintype "bidirectional"))
      (node (ref "IC5") (pin "14") (pinfunction "AGND_14") (pintype "bidirectional"))
      (node (ref "IC5") (pin "9") (pinfunction "DGND_9") (pintype "bidirectional"))
      (node (ref "IC6") (pin "14") (pinfunction "AGND_14") (pintype "bidirectional"))
      (node (ref "IC6") (pin "9") (pinfunction "DGND_9") (pintype "bidirectional"))
      (node (ref "IN/OUT") (pin "1") (pinfunction "1_1") (pintype "bidirectional"))
      (node (ref "J1") (pin "2") (pinfunction "2_2") (pintype "bidirectional"))
      (node (ref "J1") (pin "3") (pinfunction "MNT_1_3") (pintype "bidirectional"))
      (node (ref "J1") (pin "4") (pinfunction "MNT_2_4") (pintype "bidirectional"))
      (node (ref "JOYSTICK1") (pin "1") (pinfunction "1_1") (pintype "bidirectional"))
      (node (ref "JOYSTICK1") (pin "4") (pinfunction "4_4") (pintype "bidirectional"))
      (node (ref "JOYSTICK2") (pin "1") (pinfunction "1_1") (pintype "bidirectional"))
      (node (ref "JOYSTICK2") (pin "4") (pinfunction "4_4") (pintype "bidirectional"))
      (node (ref "POT_SIG_1") (pin "1") (pinfunction "1_1") (pintype "bidirectional"))
      (node (ref "POT_SIG_1") (pin "MP1") (pinfunction "MP1_MP1") (pintype "bidirectional"))
      (node (ref "POT_SIG_1") (pin "MP2") (pinfunction "MP2_MP2") (pintype "bidirectional"))
      (node (ref "POT_SIG_2") (pin "1") (pinfunction "1_1") (pintype "bidirectional"))
      (node (ref "RST") (pin "A") (pinfunction "P_A") (pintype "passive"))
      (node (ref "RST") (pin "A'") (pinfunction "P1_A'") (pintype "passive"))
      (node (ref "SWITCHES") (pin "1") (pinfunction "1_1") (pintype "bidirectional"))
      (node (ref "U1") (pin "2") (pinfunction "GND_2") (pintype "passive"))
      (node (ref "U2") (pin "2") (pinfunction "GND_2") (pintype "passive"))
    )
    (net (code "64") (name "VIN") (class "Default")
      (node (ref "C1") (pin "1") (pinfunction "1_1") (pintype "passive"))
      (node (ref "C21") (pin "1") (pinfunction "1_1") (pintype "passive"))
      (node (ref "C23") (pin "1") (pinfunction "1_1") (pintype "passive"))
      (node (ref "C3") (pin "1") (pinfunction "1_1") (pintype "passive"))
      (node (ref "J1") (pin "1") (pinfunction "1_1") (pintype "bidirectional"))
      (node (ref "U1") (pin "1") (pinfunction "VIN_1") (pintype "passive"))
      (node (ref "U1") (pin "3") (pinfunction "EN_3") (pintype "passive"))
      (node (ref "U2") (pin "1") (pinfunction "VIN_1") (pintype "passive"))
      (node (ref "U2") (pin "3") (pinfunction "EN_3") (pintype "passive"))
    )
    (net (code "65") (name "unconnected-(IC1-ANT_{slash}_N{slash}C-Pad1)") (class "Default")
      (node (ref "IC1") (pin "1") (pinfunction "ANT_/_N/C_1") (pintype "bidirectional"))
    )
    (net (code "66") (name "unconnected-(IC1-DIO2-Pad8)") (class "Default")
      (node (ref "IC1") (pin "8") (pinfunction "DIO2_8") (pintype "bidirectional"))
    )
    (net (code "67") (name "unconnected-(IC1-DIO3-Pad9)") (class "Default")
      (node (ref "IC1") (pin "9") (pinfunction "DIO3_9") (pintype "bidirectional"))
    )
    (net (code "68") (name "unconnected-(IC1-N{slash}C_1-Pad4)") (class "Default")
      (node (ref "IC1") (pin "4") (pinfunction "N/C_1_4") (pintype "bidirectional"))
    )
    (net (code "69") (name "unconnected-(IC1-N{slash}C_2-Pad5)") (class "Default")
      (node (ref "IC1") (pin "5") (pinfunction "N/C_2_5") (pintype "bidirectional"))
    )
    (net (code "70") (name "unconnected-(IC1-N{slash}C_3-Pad10)") (class "Default")
      (node (ref "IC1") (pin "10") (pinfunction "N/C_3_10") (pintype "bidirectional"))
    )
    (net (code "71") (name "unconnected-(IC1-N{slash}C_4-Pad11)") (class "Default")
      (node (ref "IC1") (pin "11") (pinfunction "N/C_4_11") (pintype "bidirectional"))
    )
    (net (code "72") (name "unconnected-(IC2-EP-Pad29)") (class "Default")
      (node (ref "IC2") (pin "29") (pinfunction "EP_29") (pintype "bidirectional"))
    )
    (net (code "73") (name "unconnected-(IC2-GPA0-Pad17)") (class "Default")
      (node (ref "IC2") (pin "17") (pinfunction "GPA0_17") (pintype "bidirectional"))
    )
    (net (code "74") (name "unconnected-(IC2-GPB0-Pad25)") (class "Default")
      (node (ref "IC2") (pin "25") (pinfunction "GPB0_25") (pintype "bidirectional"))
    )
    (net (code "75") (name "unconnected-(IC2-INTA-Pad16)") (class "Default")
      (node (ref "IC2") (pin "16") (pinfunction "INTA_16") (pintype "bidirectional"))
    )
    (net (code "76") (name "unconnected-(IC2-INTB-Pad15)") (class "Default")
      (node (ref "IC2") (pin "15") (pinfunction "INTB_15") (pintype "bidirectional"))
    )
    (net (code "77") (name "unconnected-(IC3-EP-Pad29)") (class "Default")
      (node (ref "IC3") (pin "29") (pinfunction "EP_29") (pintype "bidirectional"))
    )
    (net (code "78") (name "unconnected-(IC3-GPA6-Pad23)") (class "Default")
      (node (ref "IC3") (pin "23") (pinfunction "GPA6_23") (pintype "bidirectional"))
    )
    (net (code "79") (name "unconnected-(IC3-GPA7-Pad24)") (class "Default")
      (node (ref "IC3") (pin "24") (pinfunction "GPA7_24") (pintype "bidirectional"))
    )
    (net (code "80") (name "unconnected-(IC3-GPB5-Pad2)") (class "Default")
      (node (ref "IC3") (pin "2") (pinfunction "GPB5_2") (pintype "bidirectional"))
    )
    (net (code "81") (name "unconnected-(IC3-GPB6-Pad3)") (class "Default")
      (node (ref "IC3") (pin "3") (pinfunction "GPB6_3") (pintype "bidirectional"))
    )
    (net (code "82") (name "unconnected-(IC3-GPB7-Pad4)") (class "Default")
      (node (ref "IC3") (pin "4") (pinfunction "GPB7_4") (pintype "bidirectional"))
    )
    (net (code "83") (name "unconnected-(IC3-INTA-Pad16)") (class "Default")
      (node (ref "IC3") (pin "16") (pinfunction "INTA_16") (pintype "bidirectional"))
    )
    (net (code "84") (name "unconnected-(IC3-INTB-Pad15)") (class "Default")
      (node (ref "IC3") (pin "15") (pinfunction "INTB_15") (pintype "bidirectional"))
    )
    (net (code "85") (name "unconnected-(IC4-NC_1-Pad17)") (class "Default")
      (node (ref "IC4") (pin "17") (pinfunction "NC_1_17") (pintype "bidirectional"))
    )
    (net (code "86") (name "unconnected-(IC4-NC_2-Pad18)") (class "Default")
      (node (ref "IC4") (pin "18") (pinfunction "NC_2_18") (pintype "bidirectional"))
    )
    (net (code "87") (name "unconnected-(IC4-NC_3-Pad19)") (class "Default")
      (node (ref "IC4") (pin "19") (pinfunction "NC_3_19") (pintype "bidirectional"))
    )
    (net (code "88") (name "unconnected-(IC4-NC_4-Pad20)") (class "Default")
      (node (ref "IC4") (pin "20") (pinfunction "NC_4_20") (pintype "bidirectional"))
    )
    (net (code "89") (name "unconnected-(IC4-NC_5-Pad21)") (class "Default")
      (node (ref "IC4") (pin "21") (pinfunction "NC_5_21") (pintype "bidirectional"))
    )
    (net (code "90") (name "unconnected-(IC4-NC_6-Pad22)") (class "Default")
      (node (ref "IC4") (pin "22") (pinfunction "NC_6_22") (pintype "bidirectional"))
    )
    (net (code "91") (name "unconnected-(IC4-NC_7-Pad27)") (class "Default")
      (node (ref "IC4") (pin "27") (pinfunction "NC_7_27") (pintype "bidirectional"))
    )
    (net (code "92") (name "unconnected-(IC4-NC_8-Pad28)") (class "Default")
      (node (ref "IC4") (pin "28") (pinfunction "NC_8_28") (pintype "bidirectional"))
    )
    (net (code "93") (name "unconnected-(IC4-NC_9-Pad32)") (class "Default")
      (node (ref "IC4") (pin "32") (pinfunction "NC_9_32") (pintype "bidirectional"))
    )
    (net (code "94") (name "unconnected-(IC5-CH6-Pad7)") (class "Default")
      (node (ref "IC5") (pin "7") (pinfunction "CH6_7") (pintype "bidirectional"))
    )
    (net (code "95") (name "unconnected-(IC5-CH7-Pad8)") (class "Default")
      (node (ref "IC5") (pin "8") (pinfunction "CH7_8") (pintype "bidirectional"))
    )
    (net (code "96") (name "unconnected-(U1-NC-Pad4)") (class "Default")
      (node (ref "U1") (pin "4") (pinfunction "NC_4") (pintype "passive"))
    )
    (net (code "97") (name "unconnected-(U2-NC-Pad4)") (class "Default")
      (node (ref "U2") (pin "4") (pinfunction "NC_4") (pintype "passive"))
    )
  )
)
